# Adafruit_DRV2605L_STEMMA_QT.net
KiCad netlist of a schematic drawn in EAGLE
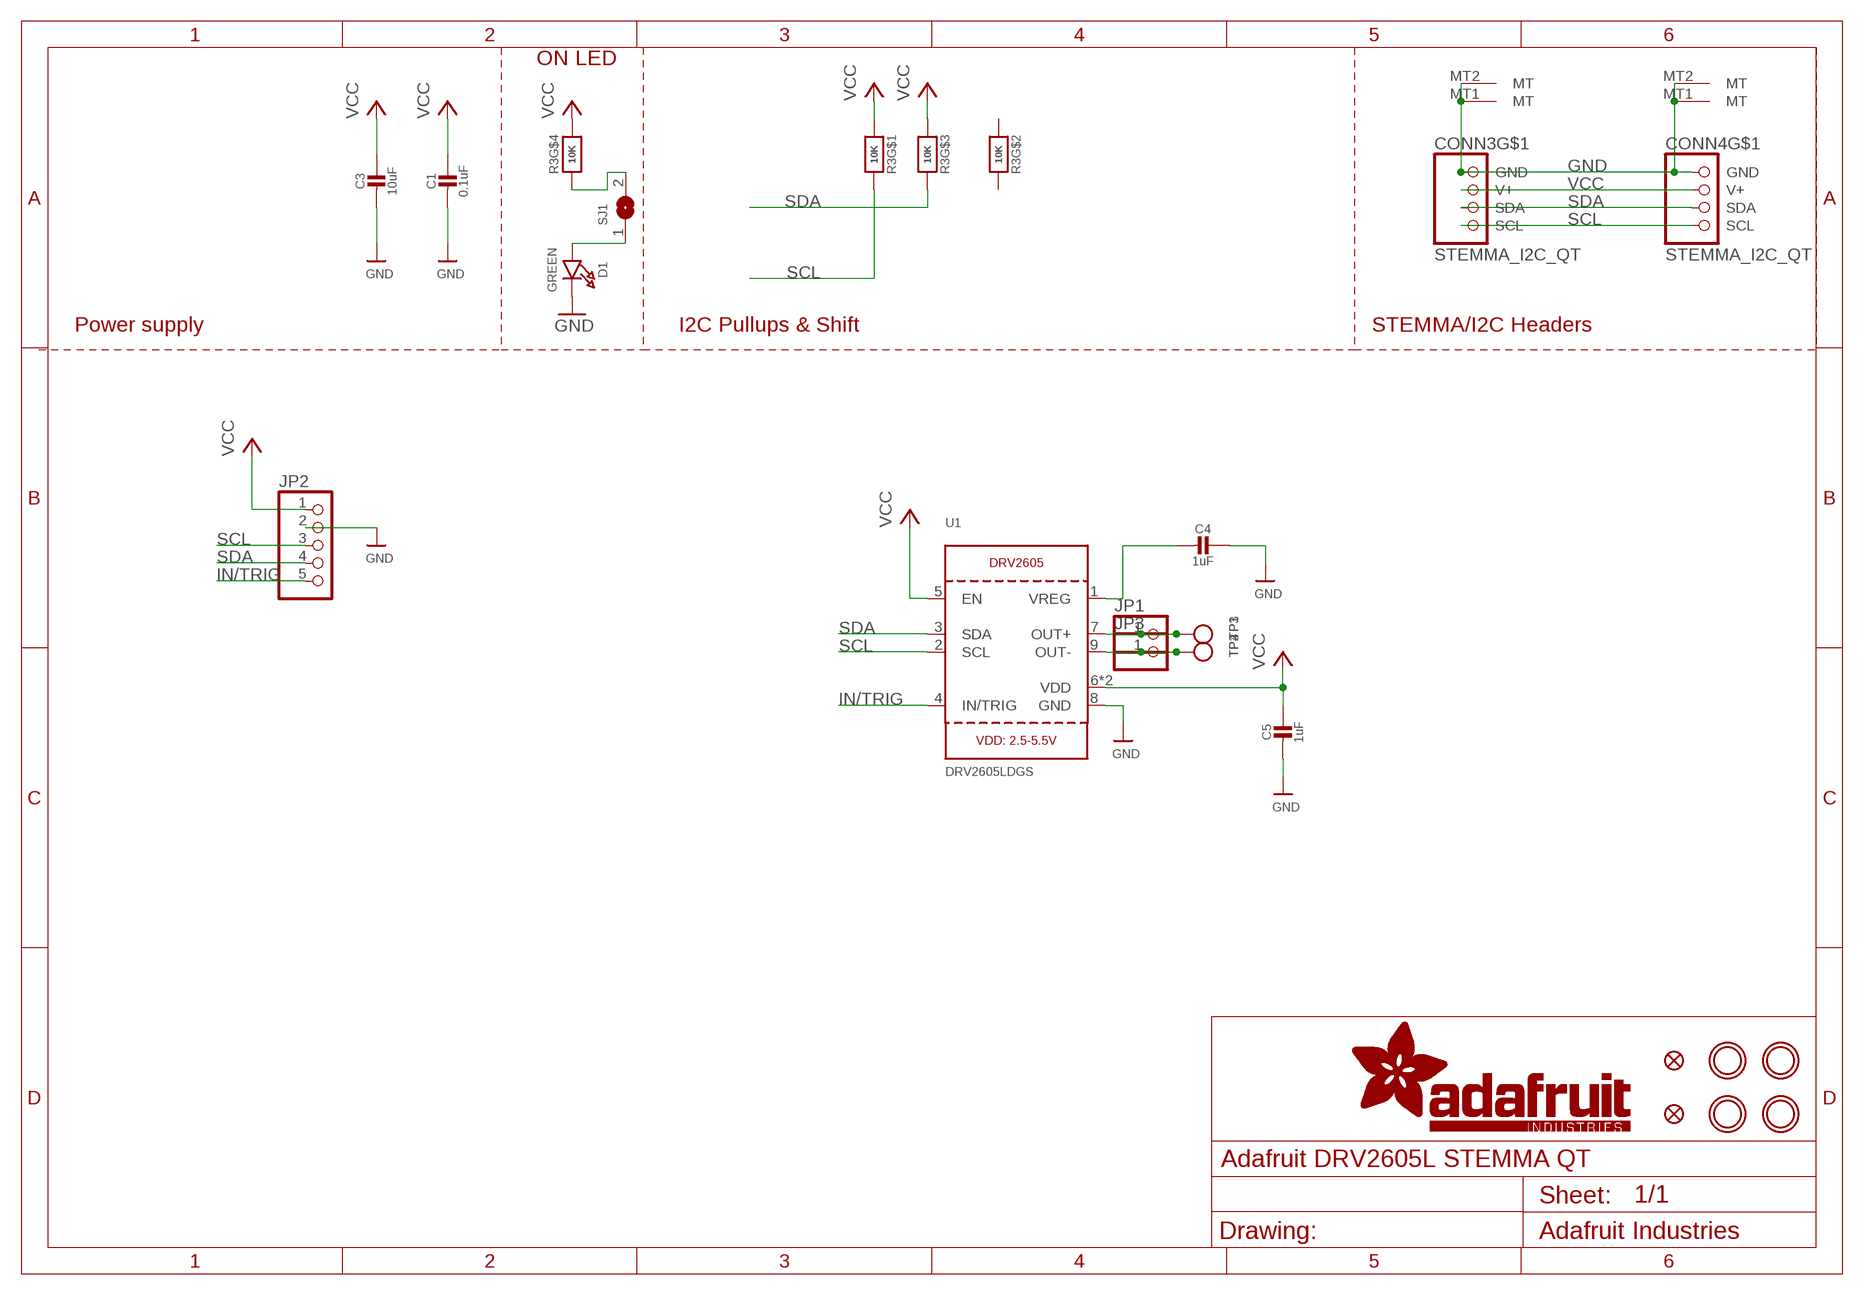
[diagram p0: schematic, sheet 1]

(export (version "E")
  (design (tool "Eeschema 10.0.6"))
  (components
    (comp (ref "C1")
      (value "0.1uF")
      (footprint "eagle-import:0603-NO")
      (libsource (lib "eagle-import") (part "CAP_CERAMIC0603_NO"))
    )
    (comp (ref "C3")
      (value "10uF")
      (footprint "eagle-import:0805-NO")
      (libsource (lib "eagle-import") (part "CAP_CERAMIC0805-NOOUTLINE"))
    )
    (comp (ref "C4")
      (value "1uF")
      (footprint "eagle-import:0603-NO")
      (libsource (lib "eagle-import") (part "CAP_CERAMIC0603_NO"))
    )
    (comp (ref "C5")
      (value "1uF")
      (footprint "eagle-import:0603-NO")
      (libsource (lib "eagle-import") (part "CAP_CERAMIC0603_NO"))
    )
    (comp (ref "CONN3")
      (value "STEMMA_I2C_QT")
      (footprint "eagle-import:JST_SH4")
      (libsource (lib "eagle-import") (part "STEMMA_I2C_QT"))
    )
    (comp (ref "CONN4")
      (value "STEMMA_I2C_QT")
      (footprint "eagle-import:JST_SH4")
      (libsource (lib "eagle-import") (part "STEMMA_I2C_QT"))
    )
    (comp (ref "D1")
      (value "GREEN")
      (footprint "eagle-import:CHIPLED_0603_NOOUTLINE")
      (libsource (lib "eagle-import") (part "LED0603_NOOUTLINE"))
    )
    (comp (ref "FID3")
      (value "FIDUCIAL_1MM")
      (footprint "eagle-import:FIDUCIAL_1MM")
      (libsource (lib "eagle-import") (part "FIDUCIAL_1MM"))
    )
    (comp (ref "FID4")
      (value "FIDUCIAL_1MM")
      (footprint "eagle-import:FIDUCIAL_1MM")
      (libsource (lib "eagle-import") (part "FIDUCIAL_1MM"))
    )
    (comp (ref "JP1")
      (value "HEADER-1X1")
      (footprint "eagle-import:1X01_OVAL")
      (libsource (lib "eagle-import") (part "HEADER-1X1"))
    )
    (comp (ref "JP2")
      (value "HEADER-1X576MIL")
      (footprint "eagle-import:1X05_ROUND_76")
      (libsource (lib "eagle-import") (part "HEADER-1X576MIL"))
    )
    (comp (ref "JP3")
      (value "HEADER-1X1")
      (footprint "eagle-import:1X01_OVAL")
      (libsource (lib "eagle-import") (part "HEADER-1X1"))
    )
    (comp (ref "R3")
      (value "10K")
      (footprint "eagle-import:RESPACK_4X0603")
      (libsource (lib "eagle-import") (part "RESISTOR_4PACK"))
    )
    (comp (ref "SJ1")
      (value "SOLDERJUMPERCLOSED")
      (footprint "eagle-import:SOLDERJUMPER_CLOSEDWIRE")
      (libsource (lib "eagle-import") (part "SOLDERJUMPERCLOSED"))
    )
    (comp (ref "TP1")
      (value "TESTPOINTPAD2MM")
      (footprint "eagle-import:TESTPOINT_PAD_2MM")
      (libsource (lib "eagle-import") (part "TESTPOINTPAD2MM"))
    )
    (comp (ref "TP2")
      (value "TESTPOINTPAD2MM")
      (footprint "eagle-import:TESTPOINT_PAD_2MM")
      (libsource (lib "eagle-import") (part "TESTPOINTPAD2MM"))
    )
    (comp (ref "TP3")
      (value "TESTPOINTPAD2MM")
      (footprint "eagle-import:TESTPOINT_PAD_2MM")
      (libsource (lib "eagle-import") (part "TESTPOINTPAD2MM"))
    )
    (comp (ref "TP4")
      (value "TESTPOINTPAD2MM")
      (footprint "eagle-import:TESTPOINT_PAD_2MM")
      (libsource (lib "eagle-import") (part "TESTPOINTPAD2MM"))
    )
    (comp (ref "U$1")
      (value "MOUNTINGHOLE2.5")
      (footprint "eagle-import:MOUNTINGHOLE_2.5_PLATED")
      (libsource (lib "eagle-import") (part "MOUNTINGHOLE2.5"))
    )
    (comp (ref "U$17")
      (value "MOUNTINGHOLE2.5")
      (footprint "eagle-import:MOUNTINGHOLE_2.5_PLATED")
      (libsource (lib "eagle-import") (part "MOUNTINGHOLE2.5"))
    )
    (comp (ref "U$19")
      (value "MOUNTINGHOLE2.5")
      (footprint "eagle-import:MOUNTINGHOLE_2.5_PLATED")
      (libsource (lib "eagle-import") (part "MOUNTINGHOLE2.5"))
    )
    (comp (ref "U$21")
      (value "MOUNTINGHOLE2.5")
      (footprint "eagle-import:MOUNTINGHOLE_2.5_PLATED")
      (libsource (lib "eagle-import") (part "MOUNTINGHOLE2.5"))
    )
    (comp (ref "U1")
      (value "DRV2605LDGS")
      (footprint "eagle-import:PSOP10")
      (libsource (lib "eagle-import") (part "DRV2605_SOP"))
    )
  )
  (nets
    (net (code "1") (name "/IN{slash}TRIG") (class "Default")
      (node (ref "JP2") (pin "5") (pinfunction "5_5") (pintype "passive"))
      (node (ref "U1") (pin "4") (pinfunction "IN/TRIG_4") (pintype "input"))
    )
    (net (code "2") (name "/SCL") (class "Default")
      (node (ref "CONN3") (pin "4") (pinfunction "SCL_4") (pintype "passive"))
      (node (ref "CONN4") (pin "4") (pinfunction "SCL_4") (pintype "passive"))
      (node (ref "JP2") (pin "3") (pinfunction "3_3") (pintype "passive"))
      (node (ref "R3") (pin "8") (pinfunction "2_8") (pintype "passive"))
      (node (ref "U1") (pin "2") (pinfunction "SCL_2") (pintype "input"))
    )
    (net (code "3") (name "/SDA") (class "Default")
      (node (ref "CONN3") (pin "3") (pinfunction "SDA_3") (pintype "passive"))
      (node (ref "CONN4") (pin "3") (pinfunction "SDA_3") (pintype "passive"))
      (node (ref "JP2") (pin "4") (pinfunction "4_4") (pintype "passive"))
      (node (ref "R3") (pin "6") (pinfunction "2_6") (pintype "passive"))
      (node (ref "U1") (pin "3") (pinfunction "SDA_3") (pintype "bidirectional"))
    )
    (net (code "4") (name "GND") (class "Default")
      (node (ref "C1") (pin "2") (pinfunction "2_2") (pintype "passive"))
      (node (ref "C3") (pin "2") (pinfunction "2_2") (pintype "passive"))
      (node (ref "C4") (pin "1") (pinfunction "1_1") (pintype "passive"))
      (node (ref "C5") (pin "2") (pinfunction "2_2") (pintype "passive"))
      (node (ref "CONN3") (pin "1") (pinfunction "GND_1") (pintype "passive"))
      (node (ref "CONN3") (pin "MT1") (pinfunction "MT_MT1") (pintype "bidirectional"))
      (node (ref "CONN3") (pin "MT2") (pinfunction "MT_MT2") (pintype "bidirectional"))
      (node (ref "CONN4") (pin "1") (pinfunction "GND_1") (pintype "passive"))
      (node (ref "CONN4") (pin "MT1") (pinfunction "MT_MT1") (pintype "bidirectional"))
      (node (ref "CONN4") (pin "MT2") (pinfunction "MT_MT2") (pintype "bidirectional"))
      (node (ref "D1") (pin "C") (pinfunction "C_C") (pintype "passive"))
      (node (ref "JP2") (pin "2") (pinfunction "2_2") (pintype "passive"))
      (node (ref "U1") (pin "8") (pinfunction "GND_8") (pintype "power_in"))
    )
    (net (code "5") (name "Net-(D1-PadA)") (class "Default")
      (node (ref "D1") (pin "A") (pinfunction "A_A") (pintype "passive"))
      (node (ref "SJ1") (pin "1") (pinfunction "1_1") (pintype "passive"))
    )
    (net (code "6") (name "Net-(R3D-1)") (class "Default")
      (node (ref "R3") (pin "4") (pinfunction "1_4") (pintype "passive"))
      (node (ref "SJ1") (pin "2") (pinfunction "2_2") (pintype "passive"))
    )
    (net (code "7") (name "Net-(U1-OUT+)") (class "Default")
      (node (ref "JP1") (pin "1") (pinfunction "1_1") (pintype "passive"))
      (node (ref "TP1") (pin "P$1") (pinfunction "P$1_P$1") (pintype "bidirectional"))
      (node (ref "TP3") (pin "P$1") (pinfunction "P$1_P$1") (pintype "bidirectional"))
      (node (ref "U1") (pin "7") (pinfunction "OUT+_7") (pintype "output"))
    )
    (net (code "8") (name "Net-(U1-OUT-)") (class "Default")
      (node (ref "JP3") (pin "1") (pinfunction "1_1") (pintype "passive"))
      (node (ref "TP2") (pin "P$1") (pinfunction "P$1_P$1") (pintype "bidirectional"))
      (node (ref "TP4") (pin "P$1") (pinfunction "P$1_P$1") (pintype "bidirectional"))
      (node (ref "U1") (pin "9") (pinfunction "OUT-_9") (pintype "output"))
    )
    (net (code "9") (name "Net-(U1-VREG)") (class "Default")
      (node (ref "C4") (pin "2") (pinfunction "2_2") (pintype "passive"))
      (node (ref "U1") (pin "1") (pinfunction "VREG_1") (pintype "output"))
    )
    (net (code "10") (name "VCC") (class "Default")
      (node (ref "C1") (pin "1") (pinfunction "1_1") (pintype "passive"))
      (node (ref "C3") (pin "1") (pinfunction "1_1") (pintype "passive"))
      (node (ref "C5") (pin "1") (pinfunction "1_1") (pintype "passive"))
      (node (ref "CONN3") (pin "2") (pinfunction "V+_2") (pintype "passive"))
      (node (ref "CONN4") (pin "2") (pinfunction "V+_2") (pintype "passive"))
      (node (ref "JP2") (pin "1") (pinfunction "1_1") (pintype "passive"))
      (node (ref "R3") (pin "1") (pinfunction "1_1") (pintype "passive"))
      (node (ref "R3") (pin "3") (pinfunction "1_3") (pintype "passive"))
      (node (ref "R3") (pin "5") (pinfunction "2_5") (pintype "passive"))
      (node (ref "U1") (pin "10") (pinfunction "VDD_10") (pintype "power_in"))
      (node (ref "U1") (pin "5") (pinfunction "EN_5") (pintype "input"))
      (node (ref "U1") (pin "6") (pinfunction "VDD_6") (pintype "power_in"))
    )
    (net (code "11") (name "unconnected-(R3B-1-Pad2)") (class "Default")
      (node (ref "R3") (pin "2") (pinfunction "1_2") (pintype "passive"))
    )
    (net (code "12") (name "unconnected-(R3B-2-Pad7)") (class "Default")
      (node (ref "R3") (pin "7") (pinfunction "2_7") (pintype "passive"))
    )
  )
)
